# AUDIO.net
KiCad netlist of a schematic drawn in Altium Designer
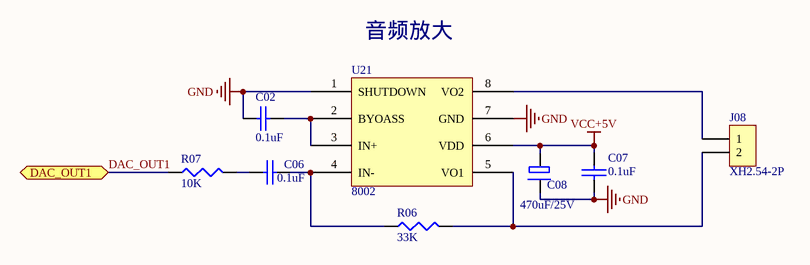
[diagram p0: AUDIO.SchDoc]

(export (version "E")
  (design (tool "Eeschema 10.0.6"))
  (components
    (comp (ref "C02")
      (value "0.1uF")
      (footprint "0603")
      (description "0603陶瓷贴片电容")
      (libsource (lib "INSPUR_PCB") (part "CAP-0603"))
    )
    (comp (ref "C06")
      (value "0.1uF")
      (footprint "0603")
      (description "0603陶瓷贴片电容")
      (libsource (lib "INSPUR_PCB") (part "CAP-0603"))
    )
    (comp (ref "C07")
      (value "0.1uF")
      (footprint "0603")
      (description "0603陶瓷贴片电容")
      (libsource (lib "INSPUR_PCB") (part "CAP-0603"))
    )
    (comp (ref "C08")
      (value "470uF/25V")
      (footprint "RB3.5-W")
      (description "470uF/25V电解电容")
      (libsource (lib "INSPUR_PCB") (part "470uF/25V"))
    )
    (comp (ref "J08")
      (value "XH2.54-2P")
      (footprint "2.54")
      (description "XH2.54-2A")
      (libsource (lib "INSPUR_PCB") (part "XH2.54-2P"))
    )
    (comp (ref "R06")
      (value "33K")
      (footprint "0603")
      (description "陶瓷贴片电阻0603封装")
      (libsource (lib "INSPUR_PCB") (part "RES-0603"))
    )
    (comp (ref "R07")
      (value "10K")
      (footprint "0603")
      (description "陶瓷贴片电阻0603封装")
      (libsource (lib "INSPUR_PCB") (part "RES-0603"))
    )
    (comp (ref "U21")
      (value "8002")
      (footprint "SO-8")
      (description "音频功放IC")
      (libsource (lib "INSPUR_PCB") (part "8002"))
    )
  )
  (nets
    (net (code "1") (name "/DAC_OUT1") (class "Default")
      (node (ref "R07") (pin "1") (pinfunction "1_1") (pintype "passive"))
    )
    (net (code "2") (name "GND") (class "Default")
      (node (ref "C02") (pin "2") (pinfunction "2_2") (pintype "passive"))
      (node (ref "C07") (pin "1") (pinfunction "1_1") (pintype "passive"))
      (node (ref "C08") (pin "2") (pintype "passive"))
      (node (ref "U21") (pin "1") (pinfunction "SHUTDOWN_1") (pintype "passive"))
      (node (ref "U21") (pin "7") (pinfunction "GND_7") (pintype "passive"))
    )
    (net (code "3") (name "Net-(C06-Pad2)") (class "Default")
      (node (ref "C06") (pin "2") (pinfunction "2_2") (pintype "passive"))
      (node (ref "R07") (pin "2") (pinfunction "2_2") (pintype "passive"))
    )
    (net (code "4") (name "Net-(U21-BYOASS)") (class "Default")
      (node (ref "C02") (pin "1") (pinfunction "1_1") (pintype "passive"))
      (node (ref "U21") (pin "2") (pinfunction "BYOASS_2") (pintype "passive"))
      (node (ref "U21") (pin "3") (pinfunction "IN+_3") (pintype "passive"))
    )
    (net (code "5") (name "Net-(U21-IN-)") (class "Default")
      (node (ref "C06") (pin "1") (pinfunction "1_1") (pintype "passive"))
      (node (ref "R06") (pin "1") (pinfunction "1_1") (pintype "passive"))
      (node (ref "U21") (pin "4") (pinfunction "IN-_4") (pintype "passive"))
    )
    (net (code "6") (name "Net-(U21-VO1)") (class "Default")
      (node (ref "J08") (pin "2") (pinfunction "2_2") (pintype "passive"))
      (node (ref "R06") (pin "2") (pinfunction "2_2") (pintype "passive"))
      (node (ref "U21") (pin "5") (pinfunction "VO1_5") (pintype "passive"))
    )
    (net (code "7") (name "Net-(U21-VO2)") (class "Default")
      (node (ref "J08") (pin "1") (pinfunction "1_1") (pintype "passive"))
      (node (ref "U21") (pin "8") (pinfunction "VO2_8") (pintype "passive"))
    )
    (net (code "8") (name "VCC+5V") (class "Default")
      (node (ref "C07") (pin "2") (pinfunction "2_2") (pintype "passive"))
      (node (ref "C08") (pin "1") (pintype "passive"))
      (node (ref "U21") (pin "6") (pinfunction "VDD_6") (pintype "passive"))
    )
  )
)
